# source_eagle.net
KiCad netlist of a schematic drawn in EAGLE
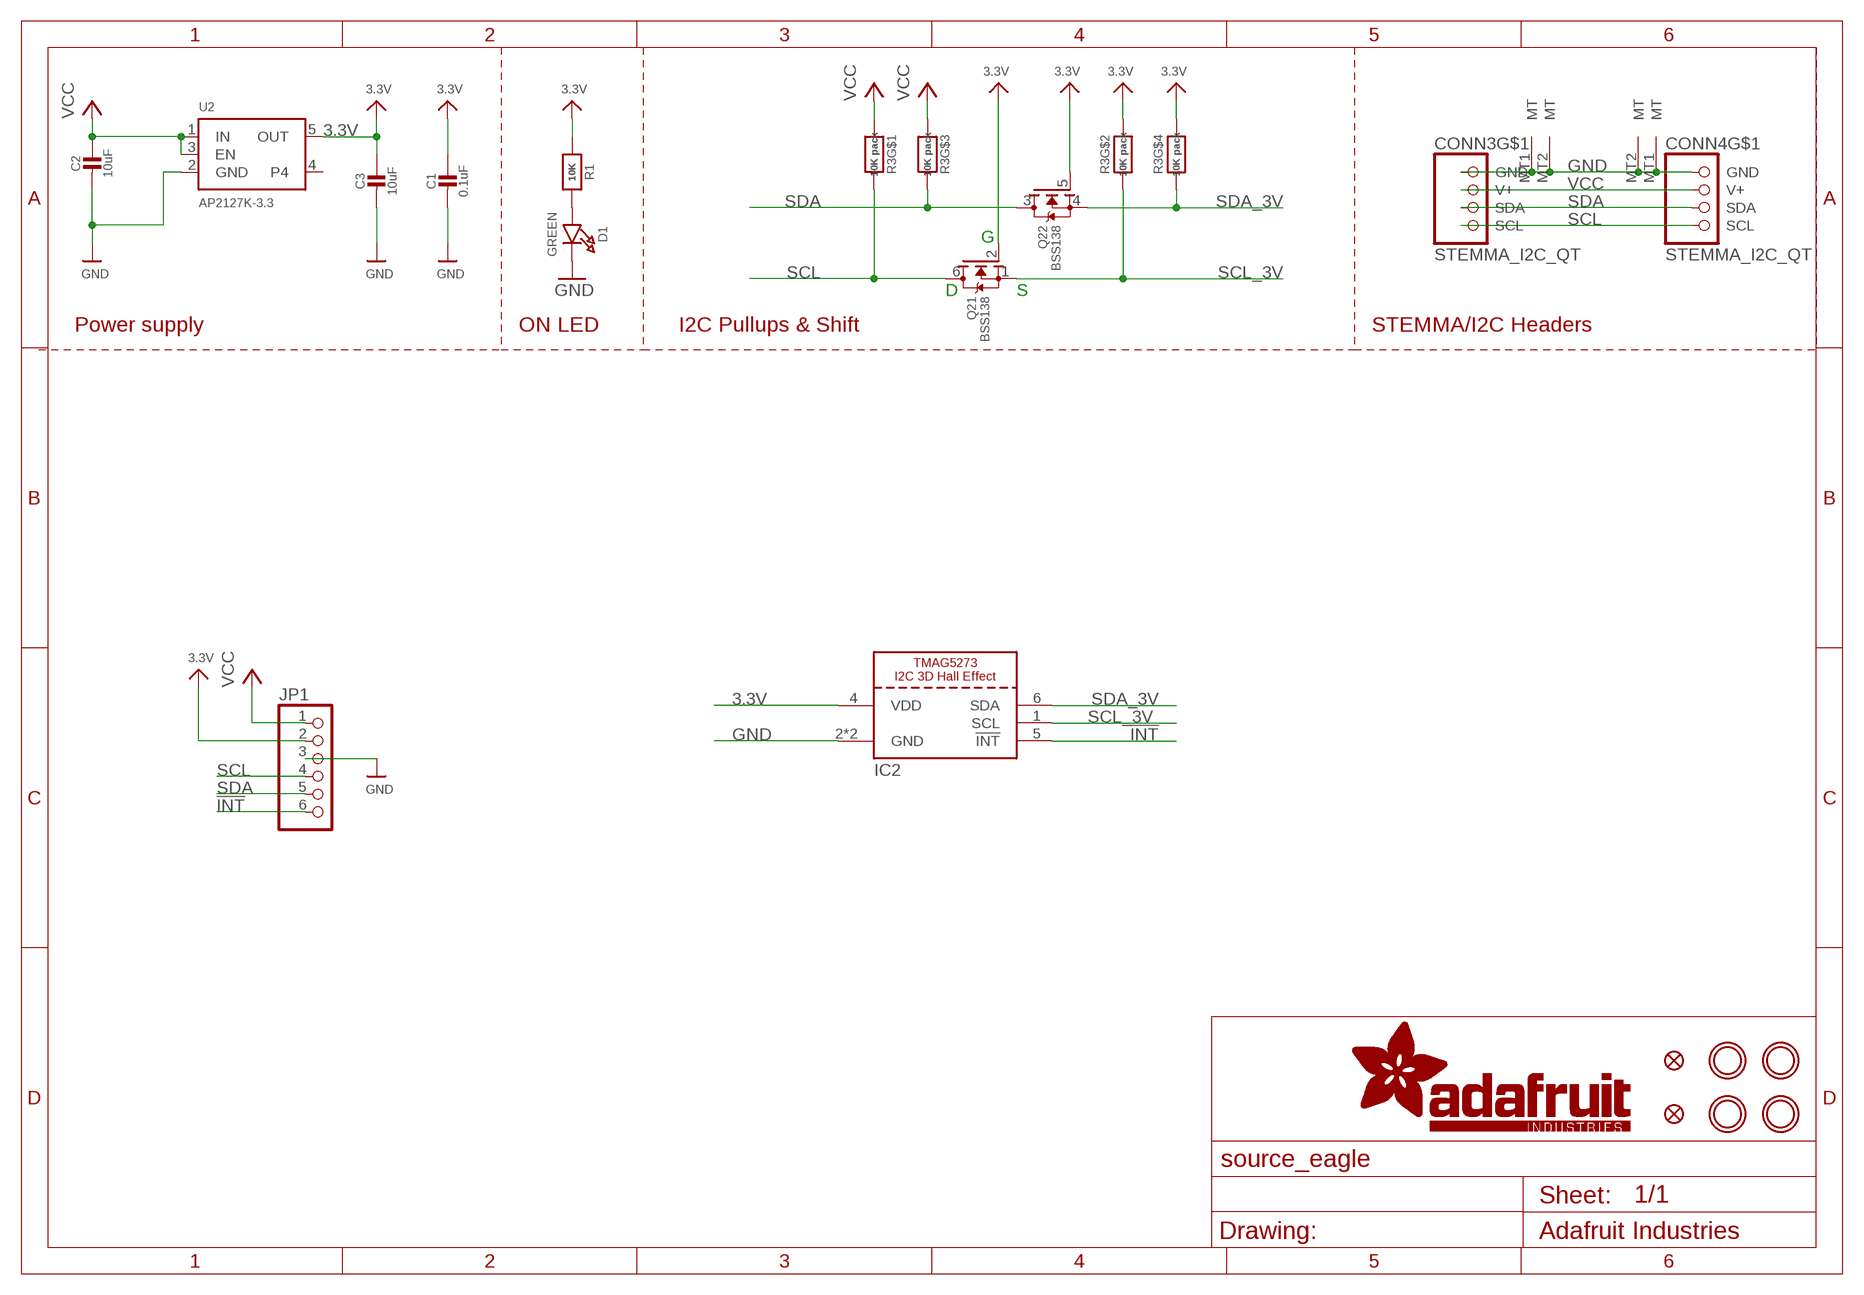
[diagram p0: schematic, sheet 1]

(export (version "E")
  (design (tool "Eeschema 10.0.6"))
  (components
    (comp (ref "C1")
      (value "0.1uF")
      (footprint "eagle-import:0603-NO")
      (libsource (lib "eagle-import") (part "CAP_CERAMIC0603_NO"))
    )
    (comp (ref "C2")
      (value "10uF")
      (footprint "eagle-import:0805-NO")
      (libsource (lib "eagle-import") (part "CAP_CERAMIC0805-NOOUTLINE"))
    )
    (comp (ref "C3")
      (value "10uF")
      (footprint "eagle-import:0805-NO")
      (libsource (lib "eagle-import") (part "CAP_CERAMIC0805-NOOUTLINE"))
    )
    (comp (ref "CONN3")
      (value "STEMMA_I2C_QT")
      (footprint "eagle-import:JST_SH4")
      (libsource (lib "eagle-import") (part "STEMMA_I2C_QT"))
    )
    (comp (ref "CONN4")
      (value "STEMMA_I2C_QT")
      (footprint "eagle-import:JST_SH4")
      (libsource (lib "eagle-import") (part "STEMMA_I2C_QT"))
    )
    (comp (ref "D1")
      (value "GREEN")
      (footprint "eagle-import:CHIPLED_0603_NOOUTLINE")
      (libsource (lib "eagle-import") (part "LED0603_NOOUTLINE"))
    )
    (comp (ref "FID3")
      (value "FIDUCIAL_0.5MM")
      (footprint "eagle-import:FIDUCIAL_0.5MM")
      (libsource (lib "eagle-import") (part "FIDUCIAL_0.5MM"))
    )
    (comp (ref "FID4")
      (value "FIDUCIAL_0.5MM")
      (footprint "eagle-import:FIDUCIAL_0.5MM")
      (libsource (lib "eagle-import") (part "FIDUCIAL_0.5MM"))
    )
    (comp (ref "IC2")
      (value "TMAG5273A2")
      (footprint "eagle-import:SOT23-6")
      (fields (field (name "ROT") "90"))
      (libsource (lib "eagle-import") (part "TMAG5273"))
    )
    (comp (ref "JP1")
      (value "HEADER-1X670MIL")
      (footprint "eagle-import:1X06_ROUND_70")
      (libsource (lib "eagle-import") (part "HEADER-1X670MIL"))
    )
    (comp (ref "Q2")
      (value "BSS138")
      (footprint "eagle-import:SOT363")
      (libsource (lib "eagle-import") (part "MOSFET-N_DUAL"))
    )
    (comp (ref "R1")
      (value "10K")
      (footprint "eagle-import:0603-NO")
      (libsource (lib "eagle-import") (part "RESISTOR_0603_NOOUT"))
    )
    (comp (ref "R3")
      (value "10K pack")
      (footprint "eagle-import:RESPACK_4X0603")
      (libsource (lib "eagle-import") (part "RESISTOR_4PACK"))
    )
    (comp (ref "U$1")
      (value "MOUNTINGHOLE2.5")
      (footprint "eagle-import:MOUNTINGHOLE_2.5_PLATED")
      (libsource (lib "eagle-import") (part "MOUNTINGHOLE2.5"))
    )
    (comp (ref "U$17")
      (value "MOUNTINGHOLE2.5")
      (footprint "eagle-import:MOUNTINGHOLE_2.5_PLATED")
      (libsource (lib "eagle-import") (part "MOUNTINGHOLE2.5"))
    )
    (comp (ref "U$19")
      (value "MOUNTINGHOLE2.5")
      (footprint "eagle-import:MOUNTINGHOLE_2.5_PLATED")
      (libsource (lib "eagle-import") (part "MOUNTINGHOLE2.5"))
    )
    (comp (ref "U$21")
      (value "MOUNTINGHOLE2.5")
      (footprint "eagle-import:MOUNTINGHOLE_2.5_PLATED")
      (libsource (lib "eagle-import") (part "MOUNTINGHOLE2.5"))
    )
    (comp (ref "U2")
      (value "AP2127K-3.3")
      (footprint "eagle-import:SOT23-5")
      (libsource (lib "eagle-import") (part "VREG_SOT23-5"))
    )
  )
  (nets
    (net (code "1") (name "/SCL") (class "Default")
      (node (ref "CONN3") (pin "4") (pinfunction "SCL_4") (pintype "passive"))
      (node (ref "CONN4") (pin "4") (pinfunction "SCL_4") (pintype "passive"))
      (node (ref "JP1") (pin "4") (pinfunction "4_4") (pintype "passive"))
      (node (ref "Q2") (pin "6") (pinfunction "D_6") (pintype "bidirectional"))
      (node (ref "R3") (pin "8") (pinfunction "2_8") (pintype "passive"))
    )
    (net (code "2") (name "/SCL_3V") (class "Default")
      (node (ref "IC2") (pin "1") (pinfunction "SCL_1") (pintype "bidirectional"))
      (node (ref "Q2") (pin "1") (pinfunction "S_1") (pintype "bidirectional"))
      (node (ref "R3") (pin "7") (pinfunction "2_7") (pintype "passive"))
    )
    (net (code "3") (name "/SDA") (class "Default")
      (node (ref "CONN3") (pin "3") (pinfunction "SDA_3") (pintype "passive"))
      (node (ref "CONN4") (pin "3") (pinfunction "SDA_3") (pintype "passive"))
      (node (ref "JP1") (pin "5") (pinfunction "5_5") (pintype "passive"))
      (node (ref "Q2") (pin "3") (pinfunction "D_3") (pintype "bidirectional"))
      (node (ref "R3") (pin "6") (pinfunction "2_6") (pintype "passive"))
    )
    (net (code "4") (name "/SDA_3V") (class "Default")
      (node (ref "IC2") (pin "6") (pinfunction "SDA_6") (pintype "bidirectional"))
      (node (ref "Q2") (pin "4") (pinfunction "S_4") (pintype "bidirectional"))
      (node (ref "R3") (pin "5") (pinfunction "2_5") (pintype "passive"))
    )
    (net (code "5") (name "/~{INT}") (class "Default")
      (node (ref "IC2") (pin "5") (pinfunction "~{INT}_5") (pintype "output"))
      (node (ref "JP1") (pin "6") (pinfunction "6_6") (pintype "passive"))
    )
    (net (code "6") (name "3.3V") (class "Default")
      (node (ref "C1") (pin "1") (pinfunction "1_1") (pintype "passive"))
      (node (ref "C3") (pin "1") (pinfunction "1_1") (pintype "passive"))
      (node (ref "IC2") (pin "4") (pinfunction "VDD_4") (pintype "power_in"))
      (node (ref "JP1") (pin "2") (pinfunction "2_2") (pintype "passive"))
      (node (ref "Q2") (pin "2") (pinfunction "G_2") (pintype "bidirectional"))
      (node (ref "Q2") (pin "5") (pinfunction "G_5") (pintype "bidirectional"))
      (node (ref "R1") (pin "1") (pinfunction "1_1") (pintype "passive"))
      (node (ref "R3") (pin "2") (pinfunction "1_2") (pintype "passive"))
      (node (ref "R3") (pin "4") (pinfunction "1_4") (pintype "passive"))
      (node (ref "U2") (pin "5") (pinfunction "OUT_5") (pintype "power_in"))
    )
    (net (code "7") (name "GND") (class "Default")
      (node (ref "C1") (pin "2") (pinfunction "2_2") (pintype "passive"))
      (node (ref "C2") (pin "2") (pinfunction "2_2") (pintype "passive"))
      (node (ref "C3") (pin "2") (pinfunction "2_2") (pintype "passive"))
      (node (ref "CONN3") (pin "1") (pinfunction "GND_1") (pintype "passive"))
      (node (ref "CONN3") (pin "MT1") (pinfunction "MT_MT1") (pintype "bidirectional"))
      (node (ref "CONN3") (pin "MT2") (pinfunction "MT_MT2") (pintype "bidirectional"))
      (node (ref "CONN4") (pin "1") (pinfunction "GND_1") (pintype "passive"))
      (node (ref "CONN4") (pin "MT1") (pinfunction "MT_MT1") (pintype "bidirectional"))
      (node (ref "CONN4") (pin "MT2") (pinfunction "MT_MT2") (pintype "bidirectional"))
      (node (ref "D1") (pin "C") (pinfunction "C_C") (pintype "passive"))
      (node (ref "IC2") (pin "2") (pinfunction "GND_2") (pintype "power_in"))
      (node (ref "IC2") (pin "3") (pinfunction "GND_3") (pintype "power_in"))
      (node (ref "JP1") (pin "3") (pinfunction "3_3") (pintype "passive"))
      (node (ref "U2") (pin "2") (pinfunction "GND_2") (pintype "power_in"))
    )
    (net (code "8") (name "Net-(D1-PadA)") (class "Default")
      (node (ref "D1") (pin "A") (pinfunction "A_A") (pintype "passive"))
      (node (ref "R1") (pin "2") (pinfunction "2_2") (pintype "passive"))
    )
    (net (code "9") (name "VCC") (class "Default")
      (node (ref "C2") (pin "1") (pinfunction "1_1") (pintype "passive"))
      (node (ref "CONN3") (pin "2") (pinfunction "V+_2") (pintype "passive"))
      (node (ref "CONN4") (pin "2") (pinfunction "V+_2") (pintype "passive"))
      (node (ref "JP1") (pin "1") (pinfunction "1_1") (pintype "passive"))
      (node (ref "R3") (pin "1") (pinfunction "1_1") (pintype "passive"))
      (node (ref "R3") (pin "3") (pinfunction "1_3") (pintype "passive"))
      (node (ref "U2") (pin "1") (pinfunction "IN_1") (pintype "power_in"))
      (node (ref "U2") (pin "3") (pinfunction "EN_3") (pintype "input"))
    )
    (net (code "10") (name "unconnected-(U2-P4-Pad4)") (class "Default")
      (node (ref "U2") (pin "4") (pinfunction "P4_4") (pintype "bidirectional"))
    )
  )
)
